# SCH_Line_follower_tutorial_2023-11-12.net
KiCad netlist of a schematic drawn in EasyEDA
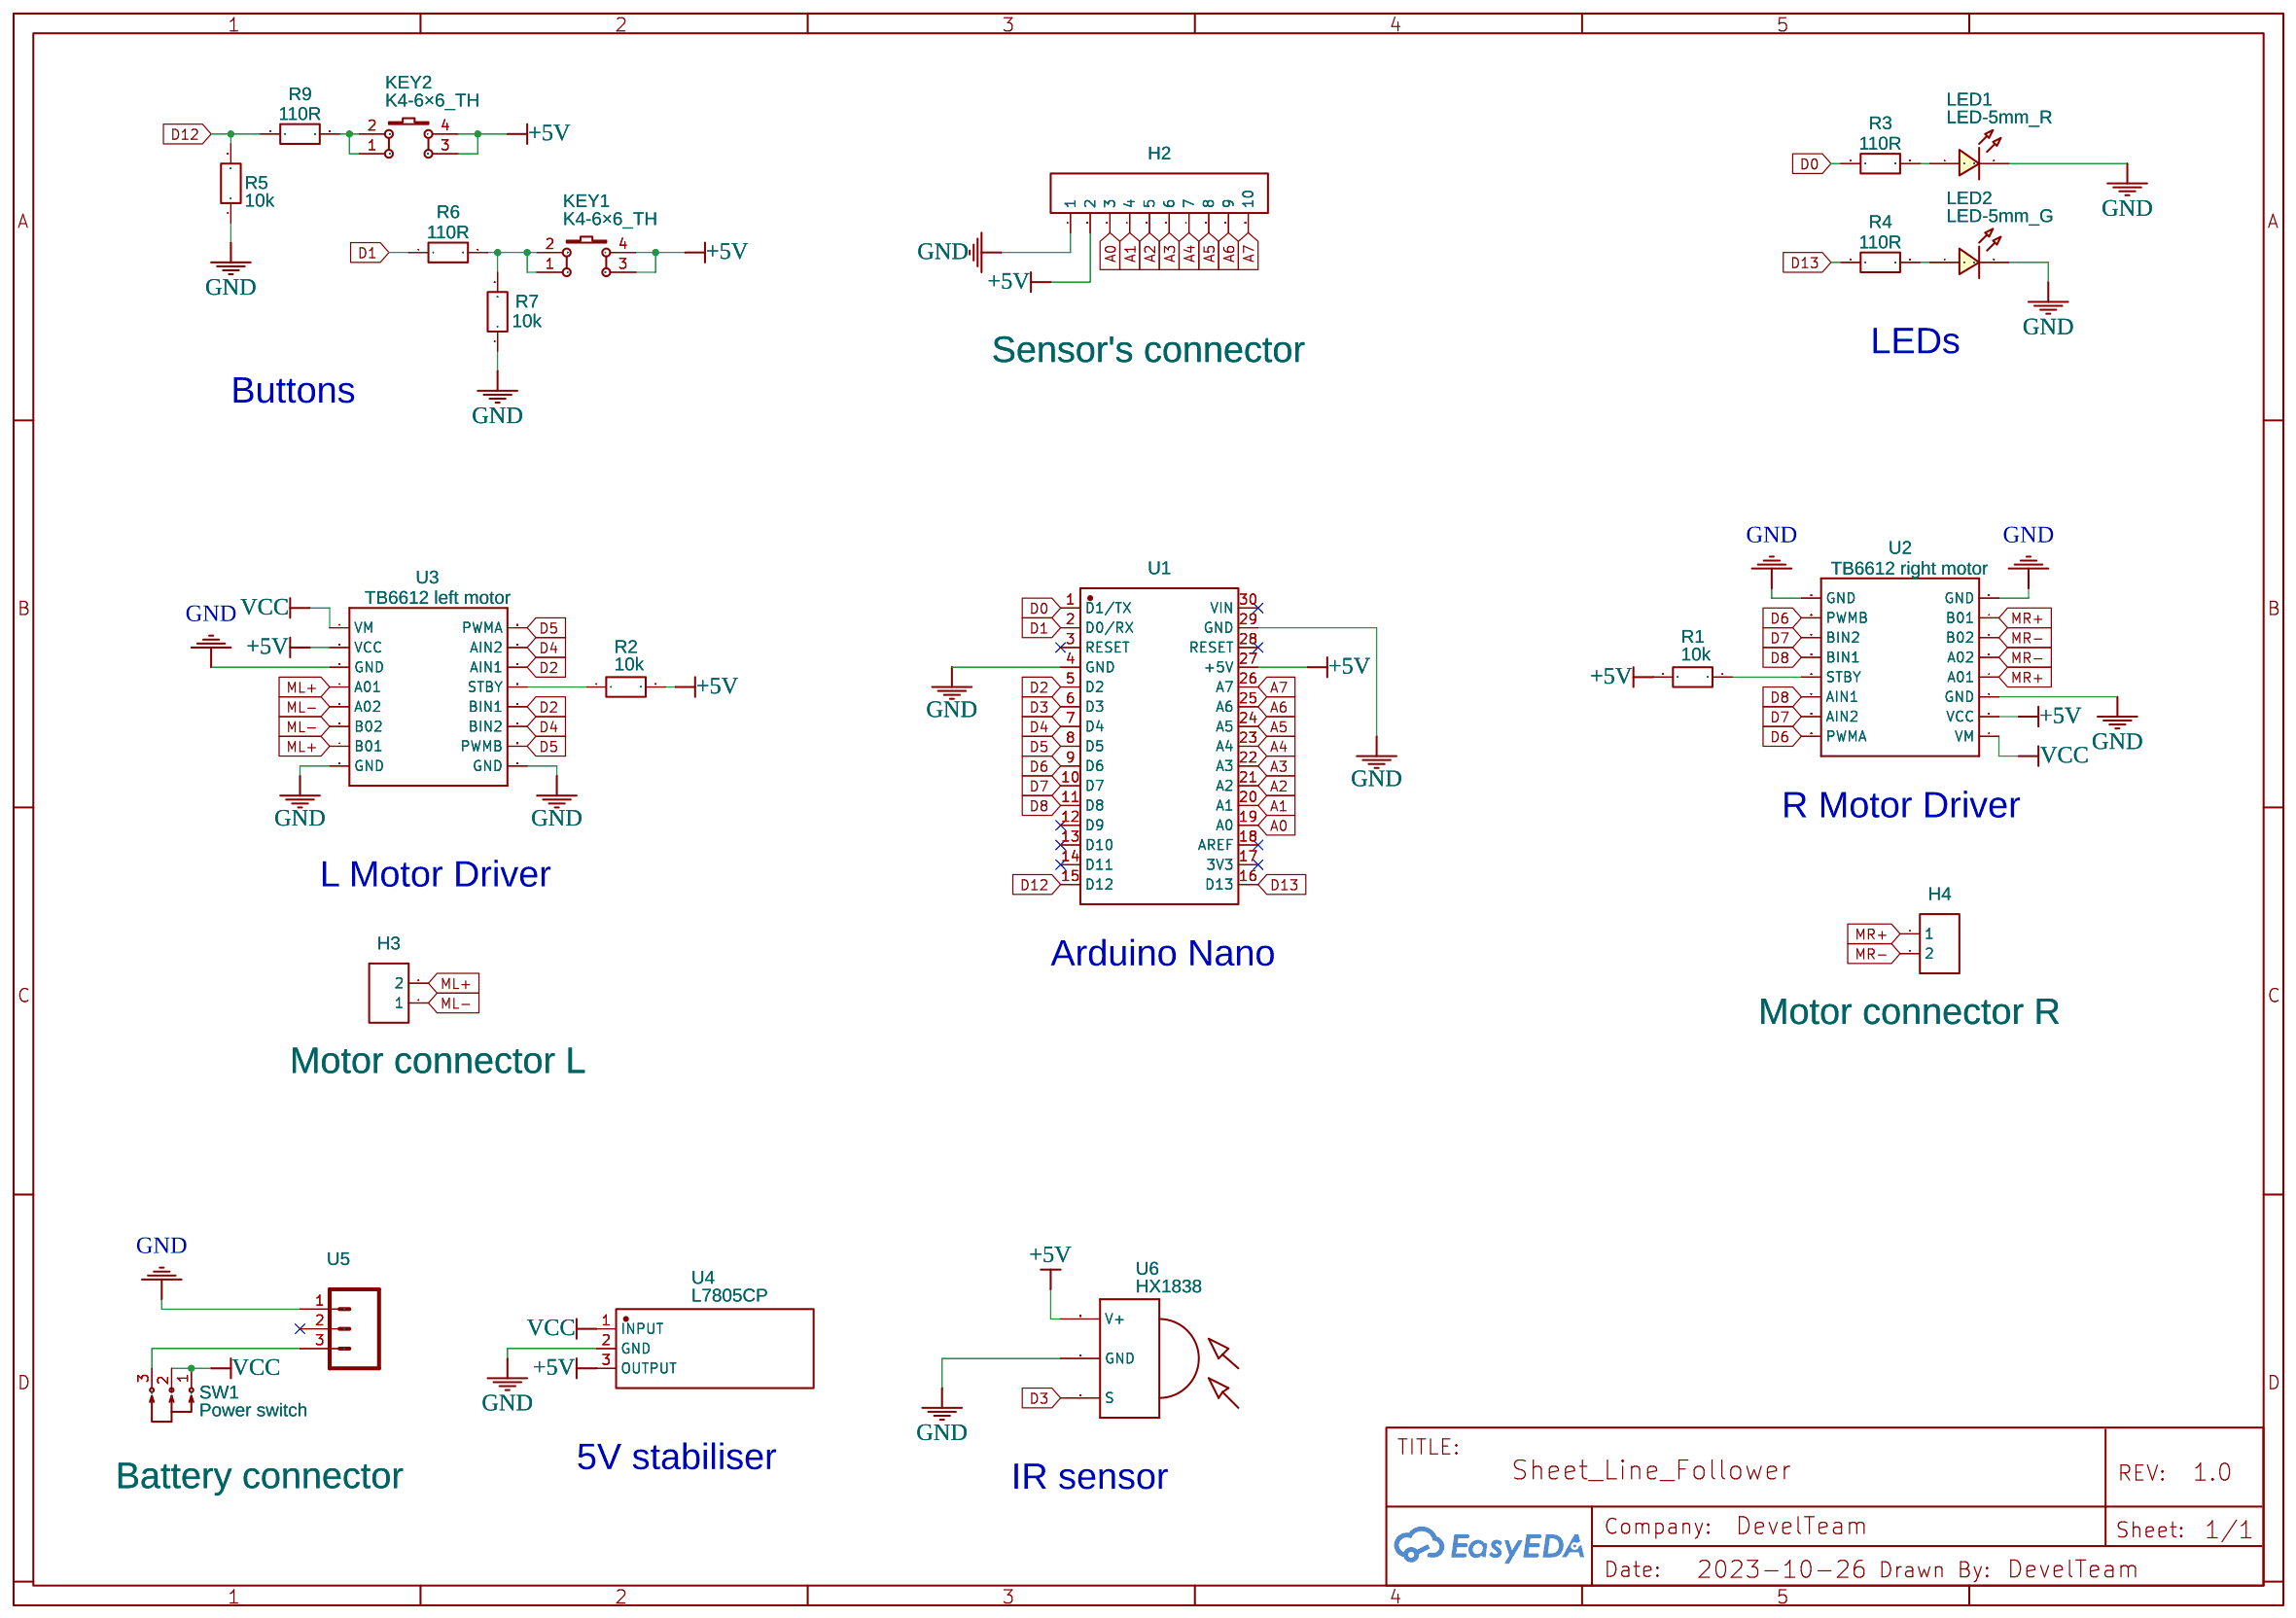
[diagram p0: schematic sheet]

(export (version "E")
  (design (tool "Eeschema 10.0.6"))
  (components
    (comp (ref "H2") (value "Sensor's connector") (libsource (lib "") (part "HDR-F-2.54_1x10")))
    (comp (ref "H3") (value "Motor connector L") (libsource (lib "") (part "HDR-F-2.54_1x2_1")))
    (comp (ref "H4") (value "Motor connector R") (libsource (lib "") (part "HDR-F-2.54_1x2")))
    (comp (ref "KEY1")
      (value "K4-6×6_TH")
      (fields (field (name "Manufacturer Part") "K2-1102DP-E4SW-04") (field (name "Manufacturer") "韩国韩荣"))
      (libsource (lib "") (part "K4-6×6_TH"))
    )
    (comp (ref "KEY2")
      (value "K4-6×6_TH")
      (fields (field (name "Manufacturer Part") "K2-1102DP-E4SW-04") (field (name "Manufacturer") "韩国韩荣"))
      (libsource (lib "") (part "K4-6×6_TH"))
    )
    (comp (ref "LED1")
      (value "LED-5mm_R")
      (fields
        (field (name "Manufacturer Part") "333-2SURD/S530-A3")
        (field (name "Manufacturer") "EVERLIGHT(台湾亿光)")
      )
      (libsource (lib "") (part "LED-TH-5mm_R"))
    )
    (comp (ref "LED2")
      (value "LED-5mm_G")
      (fields
        (field (name "Manufacturer Part") "333-2SYGD/S530-E2")
        (field (name "Manufacturer") "EVERLIGHT(台湾亿光)")
      )
      (libsource (lib "") (part "LED-TH-5mm_G"))
    )
    (comp (ref "R1") (value "10k") (libsource (lib "") (part "R_AXIAL-0.5_EU_1")))
    (comp (ref "R2") (value "10k") (libsource (lib "") (part "R_AXIAL-0.5_EU")))
    (comp (ref "R3") (value "110R") (libsource (lib "") (part "R_AXIAL-0.5_EU")))
    (comp (ref "R4") (value "110R") (libsource (lib "") (part "R_AXIAL-0.5_EU")))
    (comp (ref "R5") (value "10k") (libsource (lib "") (part "R_AXIAL-0.4_EU_1")))
    (comp (ref "R6") (value "110R") (libsource (lib "") (part "R_AXIAL-0.4_EU")))
    (comp (ref "R7") (value "10k") (libsource (lib "") (part "R_AXIAL-0.4_EU_1")))
    (comp (ref "R9") (value "110R") (libsource (lib "") (part "R_AXIAL-0.4_EU")))
    (comp (ref "SW1")
      (value "Power switch")
      (fields (field (name "Manufacturer Part") "SS12D10G4 071") (field (name "Manufacturer") "SHOU HAN(首韩)"))
      (libsource (lib "") (part "SS12D10G4 071"))
    )
    (comp (ref "U1") (value "ARDUINO_NANO") (libsource (lib "") (part "ARDUINO_NANO")))
    (comp (ref "U2") (value "TB6612 right motor") (libsource (lib "") (part "TB6612FNG 2 motor driver_1")))
    (comp (ref "U3") (value "TB6612 left motor") (libsource (lib "") (part "TB6612FNG 2 motor driver")))
    (comp (ref "U4")
      (value "L7805CP")
      (fields (field (name "Manufacturer") "ST(意法半导体)"))
      (libsource (lib "") (part "L7805CP"))
    )
    (comp (ref "U5") (value "Battery connector") (libsource (lib "") (part "BALANCE W-03 (2.54MM)")))
    (comp (ref "U6") (value "HX1838") (libsource (lib "") (part "HX1838 STAND ALONE")))
  )
  (nets
    (net (code "1") (name "+5V") (class "Default")
      (node (ref "H2") (pin "2") (pinfunction "2_2") (pintype "unspecified"))
      (node (ref "KEY1") (pin "3") (pinfunction "3_3") (pintype "unspecified"))
      (node (ref "KEY1") (pin "4") (pinfunction "4_4") (pintype "unspecified"))
      (node (ref "KEY2") (pin "3") (pinfunction "3_3") (pintype "unspecified"))
      (node (ref "KEY2") (pin "4") (pinfunction "4_4") (pintype "unspecified"))
      (node (ref "R1") (pin "2") (pinfunction "2_2") (pintype "unspecified"))
      (node (ref "R2") (pin "2") (pinfunction "2_2") (pintype "unspecified"))
      (node (ref "U1") (pin "27") (pinfunction "+5V_27") (pintype "unspecified"))
      (node (ref "U2") (pin "2") (pinfunction "VCC_2") (pintype "passive"))
      (node (ref "U3") (pin "2") (pinfunction "VCC_2") (pintype "passive"))
      (node (ref "U4") (pin "3") (pinfunction "OUTPUT_3") (pintype "unspecified"))
      (node (ref "U6") (pin "VCC") (pinfunction "V+_VCC") (pintype "unspecified"))
    )
    (net (code "2") (name "A0") (class "Default")
      (node (ref "H2") (pin "3") (pinfunction "3_3") (pintype "unspecified"))
      (node (ref "U1") (pin "19") (pinfunction "A0_19") (pintype "unspecified"))
    )
    (net (code "3") (name "A1") (class "Default")
      (node (ref "H2") (pin "4") (pinfunction "4_4") (pintype "unspecified"))
      (node (ref "U1") (pin "20") (pinfunction "A1_20") (pintype "unspecified"))
    )
    (net (code "4") (name "A2") (class "Default")
      (node (ref "H2") (pin "5") (pinfunction "5_5") (pintype "unspecified"))
      (node (ref "U1") (pin "21") (pinfunction "A2_21") (pintype "unspecified"))
    )
    (net (code "5") (name "A3") (class "Default")
      (node (ref "H2") (pin "6") (pinfunction "6_6") (pintype "unspecified"))
      (node (ref "U1") (pin "22") (pinfunction "A3_22") (pintype "unspecified"))
    )
    (net (code "6") (name "A4") (class "Default")
      (node (ref "H2") (pin "7") (pinfunction "7_7") (pintype "unspecified"))
      (node (ref "U1") (pin "23") (pinfunction "A4_23") (pintype "unspecified"))
    )
    (net (code "7") (name "A5") (class "Default")
      (node (ref "H2") (pin "8") (pinfunction "8_8") (pintype "unspecified"))
      (node (ref "U1") (pin "24") (pinfunction "A5_24") (pintype "unspecified"))
    )
    (net (code "8") (name "A6") (class "Default")
      (node (ref "H2") (pin "9") (pinfunction "9_9") (pintype "unspecified"))
      (node (ref "U1") (pin "25") (pinfunction "A6_25") (pintype "unspecified"))
    )
    (net (code "9") (name "A7") (class "Default")
      (node (ref "H2") (pin "10") (pinfunction "10_10") (pintype "unspecified"))
      (node (ref "U1") (pin "26") (pinfunction "A7_26") (pintype "unspecified"))
    )
    (net (code "10") (name "D0") (class "Default")
      (node (ref "R3") (pin "1") (pinfunction "1_1") (pintype "unspecified"))
      (node (ref "U1") (pin "1") (pinfunction "D1/TX_1") (pintype "unspecified"))
    )
    (net (code "11") (name "D1") (class "Default")
      (node (ref "R6") (pin "1") (pinfunction "1_1") (pintype "unspecified"))
      (node (ref "U1") (pin "2") (pinfunction "D0/RX_2") (pintype "unspecified"))
    )
    (net (code "12") (name "D2") (class "Default")
      (node (ref "U1") (pin "5") (pinfunction "D2_5") (pintype "unspecified"))
      (node (ref "U3") (pin "12") (pinfunction "BIN1_12") (pintype "unspecified"))
      (node (ref "U3") (pin "14") (pinfunction "AIN1_14") (pintype "unspecified"))
    )
    (net (code "13") (name "D3") (class "Default")
      (node (ref "U1") (pin "6") (pinfunction "D3_6") (pintype "unspecified"))
      (node (ref "U6") (pin "S") (pinfunction "S_S") (pintype "unspecified"))
    )
    (net (code "14") (name "D4") (class "Default")
      (node (ref "U1") (pin "7") (pinfunction "D4_7") (pintype "unspecified"))
      (node (ref "U3") (pin "11") (pinfunction "BIN2_11") (pintype "unspecified"))
      (node (ref "U3") (pin "15") (pinfunction "AIN2_15") (pintype "unspecified"))
    )
    (net (code "15") (name "D5") (class "Default")
      (node (ref "U1") (pin "8") (pinfunction "D5_8") (pintype "unspecified"))
      (node (ref "U3") (pin "10") (pinfunction "PWMB_10") (pintype "unspecified"))
      (node (ref "U3") (pin "16") (pinfunction "PWMA_16") (pintype "unspecified"))
    )
    (net (code "16") (name "D6") (class "Default")
      (node (ref "U1") (pin "9") (pinfunction "D6_9") (pintype "unspecified"))
      (node (ref "U2") (pin "10") (pinfunction "PWMB_10") (pintype "unspecified"))
      (node (ref "U2") (pin "16") (pinfunction "PWMA_16") (pintype "unspecified"))
    )
    (net (code "17") (name "D7") (class "Default")
      (node (ref "U1") (pin "10") (pinfunction "D7_10") (pintype "unspecified"))
      (node (ref "U2") (pin "11") (pinfunction "BIN2_11") (pintype "unspecified"))
      (node (ref "U2") (pin "15") (pinfunction "AIN2_15") (pintype "unspecified"))
    )
    (net (code "18") (name "D8") (class "Default")
      (node (ref "U1") (pin "11") (pinfunction "D8_11") (pintype "unspecified"))
      (node (ref "U2") (pin "12") (pinfunction "BIN1_12") (pintype "unspecified"))
      (node (ref "U2") (pin "14") (pinfunction "AIN1_14") (pintype "unspecified"))
    )
    (net (code "19") (name "D12") (class "Default")
      (node (ref "R5") (pin "2") (pinfunction "2_2") (pintype "unspecified"))
      (node (ref "R9") (pin "1") (pinfunction "1_1") (pintype "unspecified"))
      (node (ref "U1") (pin "15") (pinfunction "D12_15") (pintype "unspecified"))
    )
    (net (code "20") (name "D13") (class "Default")
      (node (ref "R4") (pin "1") (pinfunction "1_1") (pintype "unspecified"))
      (node (ref "U1") (pin "16") (pinfunction "D13_16") (pintype "unspecified"))
    )
    (net (code "21") (name "GND") (class "Default")
      (node (ref "H2") (pin "1") (pinfunction "1_1") (pintype "unspecified"))
      (node (ref "LED1") (pin "2") (pinfunction "2_2") (pintype "unspecified"))
      (node (ref "LED2") (pin "2") (pinfunction "2_2") (pintype "unspecified"))
      (node (ref "R5") (pin "1") (pinfunction "1_1") (pintype "unspecified"))
      (node (ref "R7") (pin "1") (pinfunction "1_1") (pintype "unspecified"))
      (node (ref "U1") (pin "29") (pinfunction "GND_29") (pintype "unspecified"))
      (node (ref "U1") (pin "4") (pinfunction "GND_4") (pintype "unspecified"))
      (node (ref "U2") (pin "3") (pinfunction "GND_3") (pintype "passive"))
      (node (ref "U2") (pin "8") (pinfunction "GND_8") (pintype "passive"))
      (node (ref "U2") (pin "9") (pinfunction "GND_9") (pintype "passive"))
      (node (ref "U3") (pin "3") (pinfunction "GND_3") (pintype "passive"))
      (node (ref "U3") (pin "8") (pinfunction "GND_8") (pintype "passive"))
      (node (ref "U3") (pin "9") (pinfunction "GND_9") (pintype "passive"))
      (node (ref "U4") (pin "2") (pinfunction "GND_2") (pintype "unspecified"))
      (node (ref "U5") (pin "1") (pinfunction "1_1") (pintype "unspecified"))
      (node (ref "U6") (pin "GND") (pinfunction "GND_GND") (pintype "unspecified"))
    )
    (net (code "22") (name "ML+") (class "Default")
      (node (ref "H3") (pin "2") (pinfunction "2_2") (pintype "input"))
      (node (ref "U3") (pin "4") (pinfunction "A01_4") (pintype "unspecified"))
      (node (ref "U3") (pin "7") (pinfunction "B01_7") (pintype "unspecified"))
    )
    (net (code "23") (name "ML-") (class "Default")
      (node (ref "H3") (pin "1") (pinfunction "1_1") (pintype "input"))
      (node (ref "U3") (pin "5") (pinfunction "A02_5") (pintype "unspecified"))
      (node (ref "U3") (pin "6") (pinfunction "B02_6") (pintype "unspecified"))
    )
    (net (code "24") (name "MR+") (class "Default")
      (node (ref "H4") (pin "1") (pinfunction "1_1") (pintype "input"))
      (node (ref "U2") (pin "4") (pinfunction "A01_4") (pintype "unspecified"))
      (node (ref "U2") (pin "7") (pinfunction "B01_7") (pintype "unspecified"))
    )
    (net (code "25") (name "MR-") (class "Default")
      (node (ref "H4") (pin "2") (pinfunction "2_2") (pintype "input"))
      (node (ref "U2") (pin "5") (pinfunction "A02_5") (pintype "unspecified"))
      (node (ref "U2") (pin "6") (pinfunction "B02_6") (pintype "unspecified"))
    )
    (net (code "26") (name "Net-(KEY1-Pad1)") (class "Default")
      (node (ref "KEY1") (pin "1") (pinfunction "1_1") (pintype "unspecified"))
      (node (ref "KEY1") (pin "2") (pinfunction "2_2") (pintype "unspecified"))
      (node (ref "R6") (pin "2") (pinfunction "2_2") (pintype "unspecified"))
      (node (ref "R7") (pin "2") (pinfunction "2_2") (pintype "unspecified"))
    )
    (net (code "27") (name "Net-(KEY2-Pad1)") (class "Default")
      (node (ref "KEY2") (pin "1") (pinfunction "1_1") (pintype "unspecified"))
      (node (ref "KEY2") (pin "2") (pinfunction "2_2") (pintype "unspecified"))
      (node (ref "R9") (pin "2") (pinfunction "2_2") (pintype "unspecified"))
    )
    (net (code "28") (name "Net-(LED1-Pad1)") (class "Default")
      (node (ref "LED1") (pin "1") (pinfunction "1_1") (pintype "unspecified"))
      (node (ref "R3") (pin "2") (pinfunction "2_2") (pintype "unspecified"))
    )
    (net (code "29") (name "Net-(LED2-Pad1)") (class "Default")
      (node (ref "LED2") (pin "1") (pinfunction "1_1") (pintype "unspecified"))
      (node (ref "R4") (pin "2") (pinfunction "2_2") (pintype "unspecified"))
    )
    (net (code "30") (name "Net-(SW1-Pad3)") (class "Default")
      (node (ref "SW1") (pin "3") (pinfunction "3_3") (pintype "unspecified"))
      (node (ref "U5") (pin "3") (pinfunction "3_3") (pintype "unspecified"))
    )
    (net (code "31") (name "Net-(U2-STBY)") (class "Default")
      (node (ref "R1") (pin "1") (pinfunction "1_1") (pintype "unspecified"))
      (node (ref "U2") (pin "13") (pinfunction "STBY_13") (pintype "unspecified"))
    )
    (net (code "32") (name "Net-(U3-STBY)") (class "Default")
      (node (ref "R2") (pin "1") (pinfunction "1_1") (pintype "unspecified"))
      (node (ref "U3") (pin "13") (pinfunction "STBY_13") (pintype "unspecified"))
    )
    (net (code "33") (name "VCC") (class "Default")
      (node (ref "SW1") (pin "1") (pinfunction "1_1") (pintype "unspecified"))
      (node (ref "SW1") (pin "2") (pinfunction "2_2") (pintype "unspecified"))
      (node (ref "U2") (pin "1") (pinfunction "VM_1") (pintype "passive"))
      (node (ref "U3") (pin "1") (pinfunction "VM_1") (pintype "passive"))
      (node (ref "U4") (pin "1") (pinfunction "INPUT_1") (pintype "unspecified"))
    )
    (net (code "34") (name "unconnected-(U1-3V3-Pad17)") (class "Default")
      (node (ref "U1") (pin "17") (pinfunction "3V3_17") (pintype "unspecified+no_connect"))
    )
    (net (code "35") (name "unconnected-(U1-AREF-Pad18)") (class "Default")
      (node (ref "U1") (pin "18") (pinfunction "AREF_18") (pintype "unspecified+no_connect"))
    )
    (net (code "36") (name "unconnected-(U1-D9-Pad12)") (class "Default")
      (node (ref "U1") (pin "12") (pinfunction "D9_12") (pintype "unspecified+no_connect"))
    )
    (net (code "37") (name "unconnected-(U1-D10-Pad13)") (class "Default")
      (node (ref "U1") (pin "13") (pinfunction "D10_13") (pintype "unspecified+no_connect"))
    )
    (net (code "38") (name "unconnected-(U1-D11-Pad14)") (class "Default")
      (node (ref "U1") (pin "14") (pinfunction "D11_14") (pintype "unspecified+no_connect"))
    )
    (net (code "39") (name "unconnected-(U1-RESET-Pad3)") (class "Default")
      (node (ref "U1") (pin "3") (pinfunction "RESET_3") (pintype "unspecified+no_connect"))
    )
    (net (code "40") (name "unconnected-(U1-RESET-Pad28)") (class "Default")
      (node (ref "U1") (pin "28") (pinfunction "RESET_28") (pintype "unspecified+no_connect"))
    )
    (net (code "41") (name "unconnected-(U1-VIN-Pad30)") (class "Default")
      (node (ref "U1") (pin "30") (pinfunction "VIN_30") (pintype "unspecified+no_connect"))
    )
    (net (code "42") (name "unconnected-(U5-Pad2)") (class "Default")
      (node (ref "U5") (pin "2") (pinfunction "2_2") (pintype "unspecified+no_connect"))
    )
  )
)
